# Main.net
KiCad netlist of a schematic drawn in EAGLE
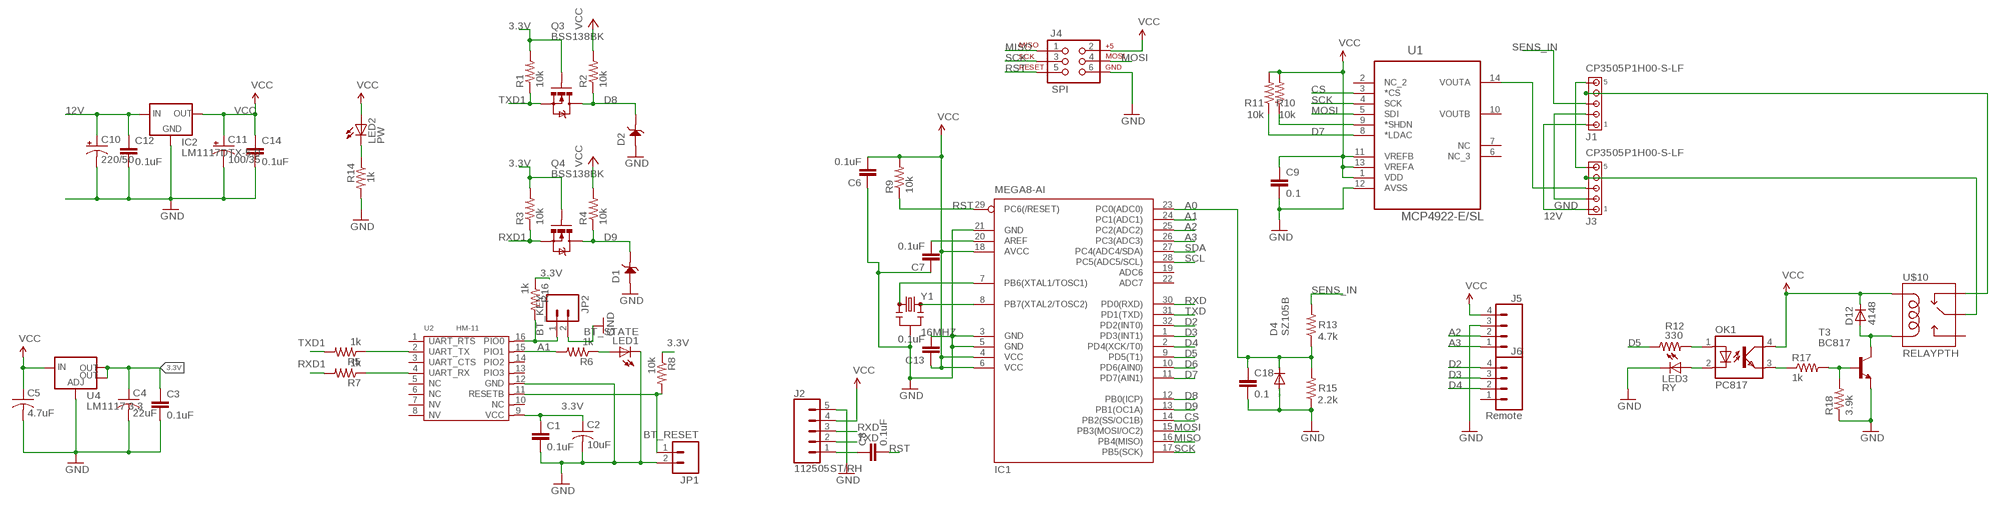
[diagram p0: schematic, sheet 1]

(export (version "E")
  (design (tool "Eeschema 10.0.6"))
  (components
    (comp (ref "C1")
      (value "0.1uF")
      (footprint "eagle-import:0805")
      (libsource (lib "eagle-import") (part "CAP0805"))
    )
    (comp (ref "C2")
      (value "10uF")
      (footprint "eagle-import:C1206")
      (libsource (lib "eagle-import") (part "C-USC1206"))
    )
    (comp (ref "C3")
      (value "0.1uF")
      (footprint "eagle-import:0805")
      (libsource (lib "eagle-import") (part "SparkFun-Passives_CAP0805"))
    )
    (comp (ref "C4")
      (value "22uF")
      (footprint "eagle-import:C1206")
      (libsource (lib "eagle-import") (part "C-USC1206"))
    )
    (comp (ref "C5")
      (value "4.7uF")
      (footprint "eagle-import:C1206")
      (libsource (lib "eagle-import") (part "C-USC1206"))
    )
    (comp (ref "C6")
      (value "0.1uF")
      (footprint "eagle-import:0805")
      (libsource (lib "eagle-import") (part "SparkFun-Passives_CAP0805"))
    )
    (comp (ref "C7")
      (value "0.1uF")
      (footprint "eagle-import:0805")
      (libsource (lib "eagle-import") (part "SparkFun-Passives_CAP0805"))
    )
    (comp (ref "C8")
      (value "0.1uF")
      (footprint "eagle-import:0805")
      (libsource (lib "eagle-import") (part "SparkFun-Passives_CAP0805"))
    )
    (comp (ref "C9")
      (value "0.1")
      (footprint "eagle-import:0805")
      (libsource (lib "eagle-import") (part "SparkFun-Passives_CAP0805"))
    )
    (comp (ref "C10")
      (value "220/50")
      (footprint "eagle-import:153CLV-1010")
      (libsource (lib "eagle-import") (part "CPOL-US153CLV-1010"))
    )
    (comp (ref "C11")
      (value "100/35")
      (footprint "eagle-import:153CLV-0605")
      (libsource (lib "eagle-import") (part "CPOL-US153CLV-0605"))
    )
    (comp (ref "C12")
      (value "0.1uF")
      (footprint "eagle-import:0805")
      (libsource (lib "eagle-import") (part "SparkFun-Passives_CAP0805"))
    )
    (comp (ref "C13")
      (value "0.1uF")
      (footprint "eagle-import:0805")
      (libsource (lib "eagle-import") (part "SparkFun-Passives_CAP0805"))
    )
    (comp (ref "C14")
      (value "0.1uF")
      (footprint "eagle-import:0805")
      (libsource (lib "eagle-import") (part "SparkFun-Passives_CAP0805"))
    )
    (comp (ref "C18")
      (value "0.1")
      (footprint "eagle-import:0805")
      (libsource (lib "eagle-import") (part "SparkFun-Passives_CAP0805"))
    )
    (comp (ref "D1")
      (value "SMF5.0A")
      (footprint "eagle-import:SOD123-2.7X1.6")
      (libsource (lib "eagle-import") (part "D-ESD-2P'CESD5V0D1'"))
    )
    (comp (ref "D2")
      (value "SMF5.0A")
      (footprint "eagle-import:SOD123-2.7X1.6")
      (libsource (lib "eagle-import") (part "D-ESD-2P'CESD5V0D1'"))
    )
    (comp (ref "D4")
      (value "SZ105B")
      (footprint "eagle-import:DO-214AC")
      (libsource (lib "eagle-import") (part "DIODE-DO-214AC"))
    )
    (comp (ref "D12")
      (value "4148")
      (footprint "eagle-import:SOD80")
      (libsource (lib "eagle-import") (part "D-SOD-80"))
    )
    (comp (ref "IC1")
      (value "MEGA8-AI")
      (footprint "eagle-import:TQFP32-08")
      (fields (field (name "MPN") "ATMEGA8-16AU"))
      (libsource (lib "eagle-import") (part "MEGA8-AI"))
    )
    (comp (ref "IC2")
      (value "LM1117DTX-5.0")
      (footprint "eagle-import:TO252")
      (libsource (lib "eagle-import") (part "LM1117DTX-3.3"))
    )
    (comp (ref "J1")
      (value "CP3505P1H00-S-LF")
      (footprint "eagle-import:1445055-5")
      (libsource (lib "eagle-import") (part "1445055-5"))
    )
    (comp (ref "J2")
      (value "112505ST/RH")
      (footprint "eagle-import:JST-5-PTH")
      (libsource (lib "eagle-import") (part "CONN_05JST"))
    )
    (comp (ref "J3")
      (value "CP3505P1H00-S-LF")
      (footprint "eagle-import:1445055-5")
      (libsource (lib "eagle-import") (part "1445055-5"))
    )
    (comp (ref "J4")
      (value "SPI")
      (footprint "eagle-import:2X3")
      (libsource (lib "eagle-import") (part "AVR_SPI_PRG_6PTH"))
    )
    (comp (ref "J5")
      (value "CONN_04JST-PTH")
      (footprint "eagle-import:JST-4-PTH")
      (libsource (lib "eagle-import") (part "CONN_04JST-PTH"))
    )
    (comp (ref "J6")
      (value "Remote")
      (footprint "eagle-import:JST-4-PTH")
      (libsource (lib "eagle-import") (part "CONN_04JST-PTH"))
    )
    (comp (ref "JP1")
      (value "BT_RESET")
      (footprint "eagle-import:1X02")
      (libsource (lib "eagle-import") (part "M02PTH"))
    )
    (comp (ref "JP2")
      (value "BT_KEY")
      (footprint "eagle-import:1X02")
      (libsource (lib "eagle-import") (part "M02PTH"))
    )
    (comp (ref "LED1")
      (value "BT_STATE")
      (footprint "eagle-import:LED3MM")
      (libsource (lib "eagle-import") (part "LED3MM"))
    )
    (comp (ref "LED2")
      (value "PW")
      (footprint "eagle-import:LED3MM")
      (libsource (lib "eagle-import") (part "LED3MM"))
    )
    (comp (ref "LED3")
      (value "RY")
      (footprint "eagle-import:LED3MM")
      (libsource (lib "eagle-import") (part "LED3MM"))
    )
    (comp (ref "OK1")
      (value "PC817")
      (footprint "eagle-import:DIL4-SMD")
      (libsource (lib "eagle-import") (part "LTV816S"))
    )
    (comp (ref "Q3")
      (value "BSS138BK")
      (footprint "eagle-import:SOT23-3")
      (libsource (lib "eagle-import") (part "MOSFET-NCHANNELBSS138"))
    )
    (comp (ref "Q4")
      (value "BSS138BK")
      (footprint "eagle-import:SOT23-3")
      (libsource (lib "eagle-import") (part "MOSFET-NCHANNELBSS138"))
    )
    (comp (ref "R1")
      (value "10k")
      (footprint "eagle-import:0805")
      (libsource (lib "eagle-import") (part "SparkFun-Resistors_RESISTOR0805-RES"))
    )
    (comp (ref "R2")
      (value "10k")
      (footprint "eagle-import:0805")
      (libsource (lib "eagle-import") (part "SparkFun-Resistors_RESISTOR0805-RES"))
    )
    (comp (ref "R3")
      (value "10k")
      (footprint "eagle-import:0805")
      (libsource (lib "eagle-import") (part "SparkFun-Resistors_RESISTOR0805-RES"))
    )
    (comp (ref "R4")
      (value "10k")
      (footprint "eagle-import:0805")
      (libsource (lib "eagle-import") (part "SparkFun-Resistors_RESISTOR0805-RES"))
    )
    (comp (ref "R5")
      (value "1k")
      (footprint "eagle-import:0805")
      (libsource (lib "eagle-import") (part "SparkFun-Resistors_RESISTOR0805-RES"))
    )
    (comp (ref "R6")
      (value "1k")
      (footprint "eagle-import:0805")
      (libsource (lib "eagle-import") (part "SparkFun-Resistors_RESISTOR0805-RES"))
    )
    (comp (ref "R7")
      (value "1k")
      (footprint "eagle-import:0805")
      (libsource (lib "eagle-import") (part "SparkFun-Resistors_RESISTOR0805-RES"))
    )
    (comp (ref "R8")
      (value "10k")
      (footprint "eagle-import:0805")
      (libsource (lib "eagle-import") (part "SparkFun-Resistors_RESISTOR0805-RES"))
    )
    (comp (ref "R9")
      (value "10k")
      (footprint "eagle-import:0805")
      (libsource (lib "eagle-import") (part "SparkFun-Resistors_RESISTOR0805-RES"))
    )
    (comp (ref "R10")
      (value "10k")
      (footprint "eagle-import:0805")
      (libsource (lib "eagle-import") (part "SparkFun-Resistors_RESISTOR0805-RES"))
    )
    (comp (ref "R11")
      (value "10k")
      (footprint "eagle-import:0805")
      (libsource (lib "eagle-import") (part "SparkFun-Resistors_RESISTOR0805-RES"))
    )
    (comp (ref "R12")
      (value "330")
      (footprint "eagle-import:0805")
      (libsource (lib "eagle-import") (part "RESISTOR0805-RES"))
    )
    (comp (ref "R13")
      (value "4.7k")
      (footprint "eagle-import:0805")
      (libsource (lib "eagle-import") (part "SparkFun-Resistors_RESISTOR0805-RES"))
    )
    (comp (ref "R14")
      (value "1k")
      (footprint "eagle-import:0805")
      (libsource (lib "eagle-import") (part "SparkFun-Resistors_RESISTOR0805-RES"))
    )
    (comp (ref "R15")
      (value "2.2k")
      (footprint "eagle-import:0805")
      (libsource (lib "eagle-import") (part "SparkFun-Resistors_RESISTOR0805-RES"))
    )
    (comp (ref "R16")
      (value "1k")
      (footprint "eagle-import:0805")
      (libsource (lib "eagle-import") (part "SparkFun-Resistors_RESISTOR0805-RES"))
    )
    (comp (ref "R17")
      (value "1k")
      (footprint "eagle-import:0805")
      (libsource (lib "eagle-import") (part "RESISTOR0805-RES"))
    )
    (comp (ref "R18")
      (value "3.9k")
      (footprint "eagle-import:0805")
      (libsource (lib "eagle-import") (part "RESISTOR0805-RES"))
    )
    (comp (ref "T3")
      (value "BC817")
      (footprint "eagle-import:SOT23-BEC")
      (libsource (lib "eagle-import") (part "-NPN-SOT23-BECBC817-16"))
    )
    (comp (ref "U$10")
      (value "RELAYPTH")
      (footprint "eagle-import:SRD-05VDC-SL-C")
      (libsource (lib "eagle-import") (part "RELAYPTH"))
    )
    (comp (ref "U1")
      (value "MCP4922-E/SL")
      (footprint "eagle-import:SOIC127P600X175-14N")
      (libsource (lib "eagle-import") (part "MCP4922-E/SL"))
    )
    (comp (ref "U2")
      (value "HM-11")
      (footprint "eagle-import:16P-18.5X13.5X0.8")
      (libsource (lib "eagle-import") (part "HM-11"))
    )
    (comp (ref "U4")
      (value "LM1117 3.3")
      (footprint "eagle-import:SOT223")
      (libsource (lib "eagle-import") (part "V_REG_LM1117SOT223"))
    )
    (comp (ref "Y1")
      (value "16MHZ")
      (footprint "eagle-import:RESONATOR-SMD")
      (libsource (lib "eagle-import") (part "RESONATOR16MHZ"))
    )
  )
  (nets
    (net (code "1") (name "/12V") (class "Default")
      (node (ref "C10") (pin "+") (pinfunction "+_+") (pintype "passive"))
      (node (ref "C12") (pin "1") (pinfunction "1_1") (pintype "passive"))
      (node (ref "IC2") (pin "2") (pinfunction "IN_2") (pintype "input"))
      (node (ref "J1") (pin "1") (pinfunction "1_1") (pintype "passive"))
      (node (ref "J3") (pin "1") (pinfunction "1_1") (pintype "passive"))
    )
    (net (code "2") (name "/A0") (class "Default")
      (node (ref "C18") (pin "1") (pinfunction "1_1") (pintype "passive"))
      (node (ref "D4") (pin "C") (pinfunction "C_C") (pintype "passive"))
      (node (ref "IC1") (pin "23") (pinfunction "PC0(ADC0)_23") (pintype "bidirectional"))
      (node (ref "R13") (pin "1") (pinfunction "1_1") (pintype "passive"))
      (node (ref "R15") (pin "2") (pinfunction "2_2") (pintype "passive"))
    )
    (net (code "3") (name "/A1") (class "Default")
      (node (ref "IC1") (pin "24") (pinfunction "PC1(ADC1)_24") (pintype "bidirectional"))
      (node (ref "R6") (pin "2") (pinfunction "2_2") (pintype "passive"))
      (node (ref "U2") (pin "15") (pinfunction "PIO1_15") (pintype "bidirectional"))
    )
    (net (code "4") (name "/A2") (class "Default")
      (node (ref "IC1") (pin "25") (pinfunction "PC2(ADC2)_25") (pintype "bidirectional"))
      (node (ref "J5") (pin "2") (pinfunction "2_2") (pintype "passive"))
    )
    (net (code "5") (name "/A3") (class "Default")
      (node (ref "IC1") (pin "26") (pinfunction "PC3(ADC3)_26") (pintype "bidirectional"))
      (node (ref "J5") (pin "1") (pinfunction "1_1") (pintype "passive"))
    )
    (net (code "6") (name "/CS") (class "Default")
      (node (ref "IC1") (pin "14") (pinfunction "PB2(SS/OC1B)_14") (pintype "bidirectional"))
      (node (ref "U1") (pin "3") (pinfunction "*CS_3") (pintype "input"))
    )
    (net (code "7") (name "/D2") (class "Default")
      (node (ref "IC1") (pin "32") (pinfunction "PD2(INT0)_32") (pintype "bidirectional"))
      (node (ref "J6") (pin "4") (pinfunction "4_4") (pintype "passive"))
    )
    (net (code "8") (name "/D3") (class "Default")
      (node (ref "IC1") (pin "1") (pinfunction "PD3(INT1)_1") (pintype "bidirectional"))
      (node (ref "J6") (pin "3") (pinfunction "3_3") (pintype "passive"))
    )
    (net (code "9") (name "/D4") (class "Default")
      (node (ref "IC1") (pin "2") (pinfunction "PD4(XCK/T0)_2") (pintype "bidirectional"))
      (node (ref "J6") (pin "2") (pinfunction "2_2") (pintype "passive"))
    )
    (net (code "10") (name "/D5") (class "Default")
      (node (ref "IC1") (pin "9") (pinfunction "PD5(T1)_9") (pintype "bidirectional"))
      (node (ref "R12") (pin "1") (pinfunction "1_1") (pintype "passive"))
    )
    (net (code "11") (name "/D6") (class "Default")
      (node (ref "IC1") (pin "10") (pinfunction "PD6(AIN0)_10") (pintype "bidirectional"))
    )
    (net (code "12") (name "/D7") (class "Default")
      (node (ref "IC1") (pin "11") (pinfunction "PD7(AIN1)_11") (pintype "bidirectional"))
      (node (ref "R11") (pin "1") (pinfunction "1_1") (pintype "passive"))
      (node (ref "U1") (pin "8") (pinfunction "*LDAC_8") (pintype "input"))
    )
    (net (code "13") (name "/D8") (class "Default")
      (node (ref "D2") (pin "2") (pinfunction "2_2") (pintype "bidirectional"))
      (node (ref "IC1") (pin "12") (pinfunction "PB0(ICP)_12") (pintype "bidirectional"))
      (node (ref "Q3") (pin "3") (pinfunction "D_3") (pintype "passive"))
      (node (ref "R2") (pin "1") (pinfunction "1_1") (pintype "passive"))
    )
    (net (code "14") (name "/D9") (class "Default")
      (node (ref "D1") (pin "2") (pinfunction "2_2") (pintype "bidirectional"))
      (node (ref "IC1") (pin "13") (pinfunction "PB1(OC1A)_13") (pintype "bidirectional"))
      (node (ref "Q4") (pin "3") (pinfunction "D_3") (pintype "passive"))
      (node (ref "R4") (pin "1") (pinfunction "1_1") (pintype "passive"))
    )
    (net (code "15") (name "/MISO") (class "Default")
      (node (ref "IC1") (pin "16") (pinfunction "PB4(MISO)_16") (pintype "bidirectional"))
      (node (ref "J4") (pin "1") (pinfunction "1_1") (pintype "passive"))
    )
    (net (code "16") (name "/MOSI") (class "Default")
      (node (ref "IC1") (pin "15") (pinfunction "PB3(MOSI/OC2)_15") (pintype "bidirectional"))
      (node (ref "J4") (pin "4") (pinfunction "4_4") (pintype "passive"))
      (node (ref "U1") (pin "5") (pinfunction "SDI_5") (pintype "input"))
    )
    (net (code "17") (name "/RST") (class "Default")
      (node (ref "C8") (pin "2") (pinfunction "2_2") (pintype "passive"))
      (node (ref "IC1") (pin "29") (pinfunction "PC6(/RESET)_29") (pintype "bidirectional"))
      (node (ref "J4") (pin "5") (pinfunction "5_5") (pintype "passive"))
      (node (ref "R9") (pin "1") (pinfunction "1_1") (pintype "passive"))
    )
    (net (code "18") (name "/RXD") (class "Default")
      (node (ref "IC1") (pin "30") (pinfunction "PD0(RXD)_30") (pintype "bidirectional"))
      (node (ref "J2") (pin "3") (pinfunction "3_3") (pintype "passive"))
    )
    (net (code "19") (name "/RXD1") (class "Default")
      (node (ref "Q4") (pin "2") (pinfunction "S_2") (pintype "passive"))
      (node (ref "R3") (pin "1") (pinfunction "1_1") (pintype "passive"))
      (node (ref "R7") (pin "2") (pinfunction "2_2") (pintype "passive"))
    )
    (net (code "20") (name "/SCK") (class "Default")
      (node (ref "IC1") (pin "17") (pinfunction "PB5(SCK)_17") (pintype "bidirectional"))
      (node (ref "J4") (pin "3") (pinfunction "3_3") (pintype "passive"))
      (node (ref "U1") (pin "4") (pinfunction "SCK_4") (pintype "input"))
    )
    (net (code "21") (name "/SCL") (class "Default")
      (node (ref "IC1") (pin "28") (pinfunction "PC5(ADC5/SCL)_28") (pintype "bidirectional"))
    )
    (net (code "22") (name "/SDA") (class "Default")
      (node (ref "IC1") (pin "27") (pinfunction "PC4(ADC4/SDA)_27") (pintype "bidirectional"))
    )
    (net (code "23") (name "/SENS_IN") (class "Default")
      (node (ref "J1") (pin "3") (pinfunction "3_3") (pintype "passive"))
      (node (ref "R13") (pin "2") (pinfunction "2_2") (pintype "passive"))
    )
    (net (code "24") (name "/TXD") (class "Default")
      (node (ref "IC1") (pin "31") (pinfunction "PD1(TXD)_31") (pintype "bidirectional"))
      (node (ref "J2") (pin "2") (pinfunction "2_2") (pintype "passive"))
    )
    (net (code "25") (name "/TXD1") (class "Default")
      (node (ref "Q3") (pin "2") (pinfunction "S_2") (pintype "passive"))
      (node (ref "R1") (pin "1") (pinfunction "1_1") (pintype "passive"))
      (node (ref "R5") (pin "2") (pinfunction "2_2") (pintype "passive"))
    )
    (net (code "26") (name "3.3V") (class "Default")
      (node (ref "C1") (pin "1") (pinfunction "1_1") (pintype "passive"))
      (node (ref "C2") (pin "1") (pinfunction "1_1") (pintype "passive"))
      (node (ref "C3") (pin "1") (pinfunction "1_1") (pintype "passive"))
      (node (ref "C4") (pin "1") (pinfunction "1_1") (pintype "passive"))
      (node (ref "Q3") (pin "1") (pinfunction "G_1") (pintype "passive"))
      (node (ref "Q4") (pin "1") (pinfunction "G_1") (pintype "passive"))
      (node (ref "R1") (pin "2") (pinfunction "2_2") (pintype "passive"))
      (node (ref "R16") (pin "1") (pinfunction "1_1") (pintype "passive"))
      (node (ref "R3") (pin "2") (pinfunction "2_2") (pintype "passive"))
      (node (ref "R8") (pin "1") (pinfunction "1_1") (pintype "passive"))
      (node (ref "U2") (pin "9") (pinfunction "VCC_9") (pintype "bidirectional"))
      (node (ref "U4") (pin "2") (pinfunction "OUT_2") (pintype "output"))
      (node (ref "U4") (pin "4") (pinfunction "OUT_4") (pintype "output"))
    )
    (net (code "27") (name "GND") (class "Default")
      (node (ref "C1") (pin "2") (pinfunction "2_2") (pintype "passive"))
      (node (ref "C10") (pin "-") (pinfunction "-_-") (pintype "passive"))
      (node (ref "C11") (pin "-") (pinfunction "-_-") (pintype "passive"))
      (node (ref "C12") (pin "2") (pinfunction "2_2") (pintype "passive"))
      (node (ref "C13") (pin "2") (pinfunction "2_2") (pintype "passive"))
      (node (ref "C14") (pin "2") (pinfunction "2_2") (pintype "passive"))
      (node (ref "C18") (pin "2") (pinfunction "2_2") (pintype "passive"))
      (node (ref "C2") (pin "2") (pinfunction "2_2") (pintype "passive"))
      (node (ref "C3") (pin "2") (pinfunction "2_2") (pintype "passive"))
      (node (ref "C4") (pin "2") (pinfunction "2_2") (pintype "passive"))
      (node (ref "C5") (pin "2") (pinfunction "2_2") (pintype "passive"))
      (node (ref "C6") (pin "1") (pinfunction "1_1") (pintype "passive"))
      (node (ref "C7") (pin "1") (pinfunction "1_1") (pintype "passive"))
      (node (ref "C9") (pin "2") (pinfunction "2_2") (pintype "passive"))
      (node (ref "D1") (pin "1") (pinfunction "1_1") (pintype "bidirectional"))
      (node (ref "D2") (pin "1") (pinfunction "1_1") (pintype "bidirectional"))
      (node (ref "D4") (pin "A") (pinfunction "A_A") (pintype "passive"))
      (node (ref "IC1") (pin "21") (pinfunction "GND_21") (pintype "power_in"))
      (node (ref "IC1") (pin "3") (pinfunction "GND_3") (pintype "power_in"))
      (node (ref "IC1") (pin "5") (pinfunction "GND_5") (pintype "power_in"))
      (node (ref "IC2") (pin "1") (pinfunction "GND_1") (pintype "input"))
      (node (ref "J1") (pin "2") (pinfunction "2_2") (pintype "passive"))
      (node (ref "J2") (pin "5") (pinfunction "5_5") (pintype "passive"))
      (node (ref "J3") (pin "2") (pinfunction "2_2") (pintype "passive"))
      (node (ref "J4") (pin "6") (pinfunction "6_6") (pintype "passive"))
      (node (ref "J5") (pin "3") (pinfunction "3_3") (pintype "passive"))
      (node (ref "JP1") (pin "2") (pinfunction "2_2") (pintype "passive"))
      (node (ref "JP2") (pin "2") (pinfunction "2_2") (pintype "passive"))
      (node (ref "LED1") (pin "K") (pinfunction "C_K") (pintype "passive"))
      (node (ref "LED3") (pin "K") (pinfunction "C_K") (pintype "passive"))
      (node (ref "R14") (pin "2") (pinfunction "2_2") (pintype "passive"))
      (node (ref "R15") (pin "1") (pinfunction "1_1") (pintype "passive"))
      (node (ref "R18") (pin "1") (pinfunction "1_1") (pintype "passive"))
      (node (ref "T3") (pin "E") (pinfunction "E_E") (pintype "passive"))
      (node (ref "U1") (pin "12") (pinfunction "AVSS_12") (pintype "passive"))
      (node (ref "U2") (pin "12") (pinfunction "GND_12") (pintype "bidirectional"))
      (node (ref "U4") (pin "1") (pinfunction "ADJ_1") (pintype "input"))
      (node (ref "Y1") (pin "2") (pinfunction "2_2") (pintype "passive"))
    )
    (net (code "28") (name "Net-(C8-Pad1)") (class "Default")
      (node (ref "C8") (pin "1") (pinfunction "1_1") (pintype "passive"))
      (node (ref "J2") (pin "1") (pinfunction "1_1") (pintype "passive"))
    )
    (net (code "29") (name "Net-(D12-A)") (class "Default")
      (node (ref "D12") (pin "2") (pinfunction "A_2") (pintype "passive"))
      (node (ref "T3") (pin "C") (pinfunction "C_C") (pintype "passive"))
      (node (ref "U$10") (pin "COIL0") (pinfunction "COIL0_COIL0") (pintype "bidirectional"))
    )
    (net (code "30") (name "Net-(IC1-AREF)") (class "Default")
      (node (ref "C7") (pin "2") (pinfunction "2_2") (pintype "passive"))
      (node (ref "IC1") (pin "20") (pinfunction "AREF_20") (pintype "passive"))
    )
    (net (code "31") (name "Net-(IC1-PB6(XTAL1{slash}TOSC1))") (class "Default")
      (node (ref "IC1") (pin "7") (pinfunction "PB6(XTAL1/TOSC1)_7") (pintype "bidirectional"))
      (node (ref "Y1") (pin "1") (pinfunction "1_1") (pintype "passive"))
    )
    (net (code "32") (name "Net-(IC1-PB7(XTAL2{slash}TOSC2))") (class "Default")
      (node (ref "IC1") (pin "8") (pinfunction "PB7(XTAL2/TOSC2)_8") (pintype "bidirectional"))
      (node (ref "Y1") (pin "3") (pinfunction "3_3") (pintype "passive"))
    )
    (net (code "33") (name "Net-(J1-Pad5)") (class "Default")
      (node (ref "J1") (pin "5") (pinfunction "5_5") (pintype "passive"))
      (node (ref "J3") (pin "5") (pinfunction "5_5") (pintype "passive"))
    )
    (net (code "34") (name "Net-(J3-Pad4)") (class "Default")
      (node (ref "J3") (pin "4") (pinfunction "4_4") (pintype "passive"))
      (node (ref "U$10") (pin "SWCOMMON") (pinfunction "SWCOMMON_SWCOMMON") (pintype "bidirectional"))
    )
    (net (code "35") (name "Net-(LED1-PadA)") (class "Default")
      (node (ref "LED1") (pin "A") (pinfunction "A_A") (pintype "passive"))
      (node (ref "R6") (pin "1") (pinfunction "1_1") (pintype "passive"))
    )
    (net (code "36") (name "Net-(LED2-C)") (class "Default")
      (node (ref "LED2") (pin "K") (pinfunction "C_K") (pintype "passive"))
      (node (ref "R14") (pin "1") (pinfunction "1_1") (pintype "passive"))
    )
    (net (code "37") (name "Net-(OK1-A)") (class "Default")
      (node (ref "OK1") (pin "1") (pinfunction "A_1") (pintype "passive"))
      (node (ref "R12") (pin "2") (pinfunction "2_2") (pintype "passive"))
    )
    (net (code "38") (name "Net-(OK1-C)") (class "Default")
      (node (ref "LED3") (pin "A") (pinfunction "A_A") (pintype "passive"))
      (node (ref "OK1") (pin "2") (pinfunction "C_2") (pintype "passive"))
    )
    (net (code "39") (name "Net-(OK1-EMIT)") (class "Default")
      (node (ref "OK1") (pin "3") (pinfunction "EMIT_3") (pintype "passive"))
      (node (ref "R17") (pin "1") (pinfunction "1_1") (pintype "passive"))
    )
    (net (code "40") (name "Net-(R17-Pad2)") (class "Default")
      (node (ref "R17") (pin "2") (pinfunction "2_2") (pintype "passive"))
      (node (ref "R18") (pin "2") (pinfunction "2_2") (pintype "passive"))
      (node (ref "T3") (pin "B") (pinfunction "B_B") (pintype "passive"))
    )
    (net (code "41") (name "Net-(U$10-SWCLOSE)") (class "Default")
      (node (ref "J1") (pin "4") (pinfunction "4_4") (pintype "passive"))
      (node (ref "U$10") (pin "SWCLOSED") (pinfunction "SWCLOSE_SWCLOSED") (pintype "bidirectional"))
    )
    (net (code "42") (name "Net-(U1-*SHDN)") (class "Default")
      (node (ref "R10") (pin "1") (pinfunction "1_1") (pintype "passive"))
      (node (ref "U1") (pin "9") (pinfunction "*SHDN_9") (pintype "input"))
    )
    (net (code "43") (name "Net-(U1-VOUTA)") (class "Default")
      (node (ref "J3") (pin "3") (pinfunction "3_3") (pintype "passive"))
      (node (ref "U1") (pin "14") (pinfunction "VOUTA_14") (pintype "output"))
    )
    (net (code "44") (name "Net-(U2-PIO0)") (class "Default")
      (node (ref "JP2") (pin "1") (pinfunction "1_1") (pintype "passive"))
      (node (ref "R16") (pin "2") (pinfunction "2_2") (pintype "passive"))
      (node (ref "U2") (pin "16") (pinfunction "PIO0_16") (pintype "bidirectional"))
    )
    (net (code "45") (name "Net-(U2-RESETB)") (class "Default")
      (node (ref "JP1") (pin "1") (pinfunction "1_1") (pintype "passive"))
      (node (ref "R8") (pin "2") (pinfunction "2_2") (pintype "passive"))
      (node (ref "U2") (pin "11") (pinfunction "RESETB_11") (pintype "bidirectional"))
    )
    (net (code "46") (name "Net-(U2-UART_RX)") (class "Default")
      (node (ref "R7") (pin "1") (pinfunction "1_1") (pintype "passive"))
      (node (ref "U2") (pin "4") (pinfunction "UART_RX_4") (pintype "bidirectional"))
    )
    (net (code "47") (name "Net-(U2-UART_TX)") (class "Default")
      (node (ref "R5") (pin "1") (pinfunction "1_1") (pintype "passive"))
      (node (ref "U2") (pin "2") (pinfunction "UART_TX_2") (pintype "bidirectional"))
    )
    (net (code "48") (name "VCC") (class "Default")
      (node (ref "C11") (pin "+") (pinfunction "+_+") (pintype "passive"))
      (node (ref "C13") (pin "1") (pinfunction "1_1") (pintype "passive"))
      (node (ref "C14") (pin "1") (pinfunction "1_1") (pintype "passive"))
      (node (ref "C5") (pin "1") (pinfunction "1_1") (pintype "passive"))
      (node (ref "C6") (pin "2") (pinfunction "2_2") (pintype "passive"))
      (node (ref "C9") (pin "1") (pinfunction "1_1") (pintype "passive"))
      (node (ref "D12") (pin "1") (pinfunction "C_1") (pintype "passive"))
      (node (ref "IC1") (pin "18") (pinfunction "AVCC_18") (pintype "power_in"))
      (node (ref "IC1") (pin "4") (pinfunction "VCC_4") (pintype "power_in"))
      (node (ref "IC1") (pin "6") (pinfunction "VCC_6") (pintype "power_in"))
      (node (ref "IC2") (pin "TAB") (pinfunction "OUT_TAB") (pintype "passive"))
      (node (ref "J2") (pin "4") (pinfunction "4_4") (pintype "passive"))
      (node (ref "J4") (pin "2") (pinfunction "2_2") (pintype "passive"))
      (node (ref "J5") (pin "4") (pinfunction "4_4") (pintype "passive"))
      (node (ref "LED2") (pin "A") (pinfunction "A_A") (pintype "passive"))
      (node (ref "OK1") (pin "4") (pinfunction "COL_4") (pintype "passive"))
      (node (ref "R10") (pin "2") (pinfunction "2_2") (pintype "passive"))
      (node (ref "R11") (pin "2") (pinfunction "2_2") (pintype "passive"))
      (node (ref "R2") (pin "2") (pinfunction "2_2") (pintype "passive"))
      (node (ref "R4") (pin "2") (pinfunction "2_2") (pintype "passive"))
      (node (ref "R9") (pin "2") (pinfunction "2_2") (pintype "passive"))
      (node (ref "U$10") (pin "COIL1") (pinfunction "COIL1_COIL1") (pintype "bidirectional"))
      (node (ref "U1") (pin "1") (pinfunction "VDD_1") (pintype "power_in"))
      (node (ref "U1") (pin "11") (pinfunction "VREFB_11") (pintype "input"))
      (node (ref "U1") (pin "13") (pinfunction "VREFA_13") (pintype "input"))
      (node (ref "U4") (pin "3") (pinfunction "IN_3") (pintype "input"))
    )
    (net (code "49") (name "unconnected-(IC1-ADC6-Pad19)") (class "Default")
      (node (ref "IC1") (pin "19") (pinfunction "ADC6_19") (pintype "bidirectional"))
    )
    (net (code "50") (name "unconnected-(IC1-ADC7-Pad22)") (class "Default")
      (node (ref "IC1") (pin "22") (pinfunction "ADC7_22") (pintype "bidirectional"))
    )
    (net (code "51") (name "unconnected-(J6-Pad1)") (class "Default")
      (node (ref "J6") (pin "1") (pinfunction "1_1") (pintype "passive"))
    )
    (net (code "52") (name "unconnected-(U$10-PadSWOPEN)") (class "Default")
      (node (ref "U$10") (pin "SWOPEN") (pinfunction "SWOPEN_SWOPEN") (pintype "bidirectional"))
    )
    (net (code "53") (name "unconnected-(U1-NC-Pad7)") (class "Default")
      (node (ref "U1") (pin "7") (pinfunction "NC_7") (pintype "no_connect"))
    )
    (net (code "54") (name "unconnected-(U1-NC_2-Pad2)") (class "Default")
      (node (ref "U1") (pin "2") (pinfunction "NC_2_2") (pintype "no_connect"))
    )
    (net (code "55") (name "unconnected-(U1-NC_3-Pad6)") (class "Default")
      (node (ref "U1") (pin "6") (pinfunction "NC_3_6") (pintype "no_connect"))
    )
    (net (code "56") (name "unconnected-(U1-VOUTB-Pad10)") (class "Default")
      (node (ref "U1") (pin "10") (pinfunction "VOUTB_10") (pintype "output"))
    )
    (net (code "57") (name "unconnected-(U2-NC-Pad5)") (class "Default")
      (node (ref "U2") (pin "5") (pinfunction "NC_5") (pintype "bidirectional"))
    )
    (net (code "58") (name "unconnected-(U2-NC-Pad6)") (class "Default")
      (node (ref "U2") (pin "6") (pinfunction "NC_6") (pintype "bidirectional"))
    )
    (net (code "59") (name "unconnected-(U2-NC-Pad10)") (class "Default")
      (node (ref "U2") (pin "10") (pinfunction "NC_10") (pintype "bidirectional"))
    )
    (net (code "60") (name "unconnected-(U2-NV-Pad7)") (class "Default")
      (node (ref "U2") (pin "7") (pinfunction "NV_7") (pintype "bidirectional"))
    )
    (net (code "61") (name "unconnected-(U2-NV-Pad8)") (class "Default")
      (node (ref "U2") (pin "8") (pinfunction "NV_8") (pintype "bidirectional"))
    )
    (net (code "62") (name "unconnected-(U2-PIO2-Pad14)") (class "Default")
      (node (ref "U2") (pin "14") (pinfunction "PIO2_14") (pintype "bidirectional"))
    )
    (net (code "63") (name "unconnected-(U2-PIO3-Pad13)") (class "Default")
      (node (ref "U2") (pin "13") (pinfunction "PIO3_13") (pintype "bidirectional"))
    )
    (net (code "64") (name "unconnected-(U2-UART_CTS-Pad3)") (class "Default")
      (node (ref "U2") (pin "3") (pinfunction "UART_CTS_3") (pintype "bidirectional"))
    )
    (net (code "65") (name "unconnected-(U2-UART_RTS-Pad1)") (class "Default")
      (node (ref "U2") (pin "1") (pinfunction "UART_RTS_1") (pintype "bidirectional"))
    )
  )
)
